# var_state_eq.net
KiCad netlist of a schematic drawn in EAGLE
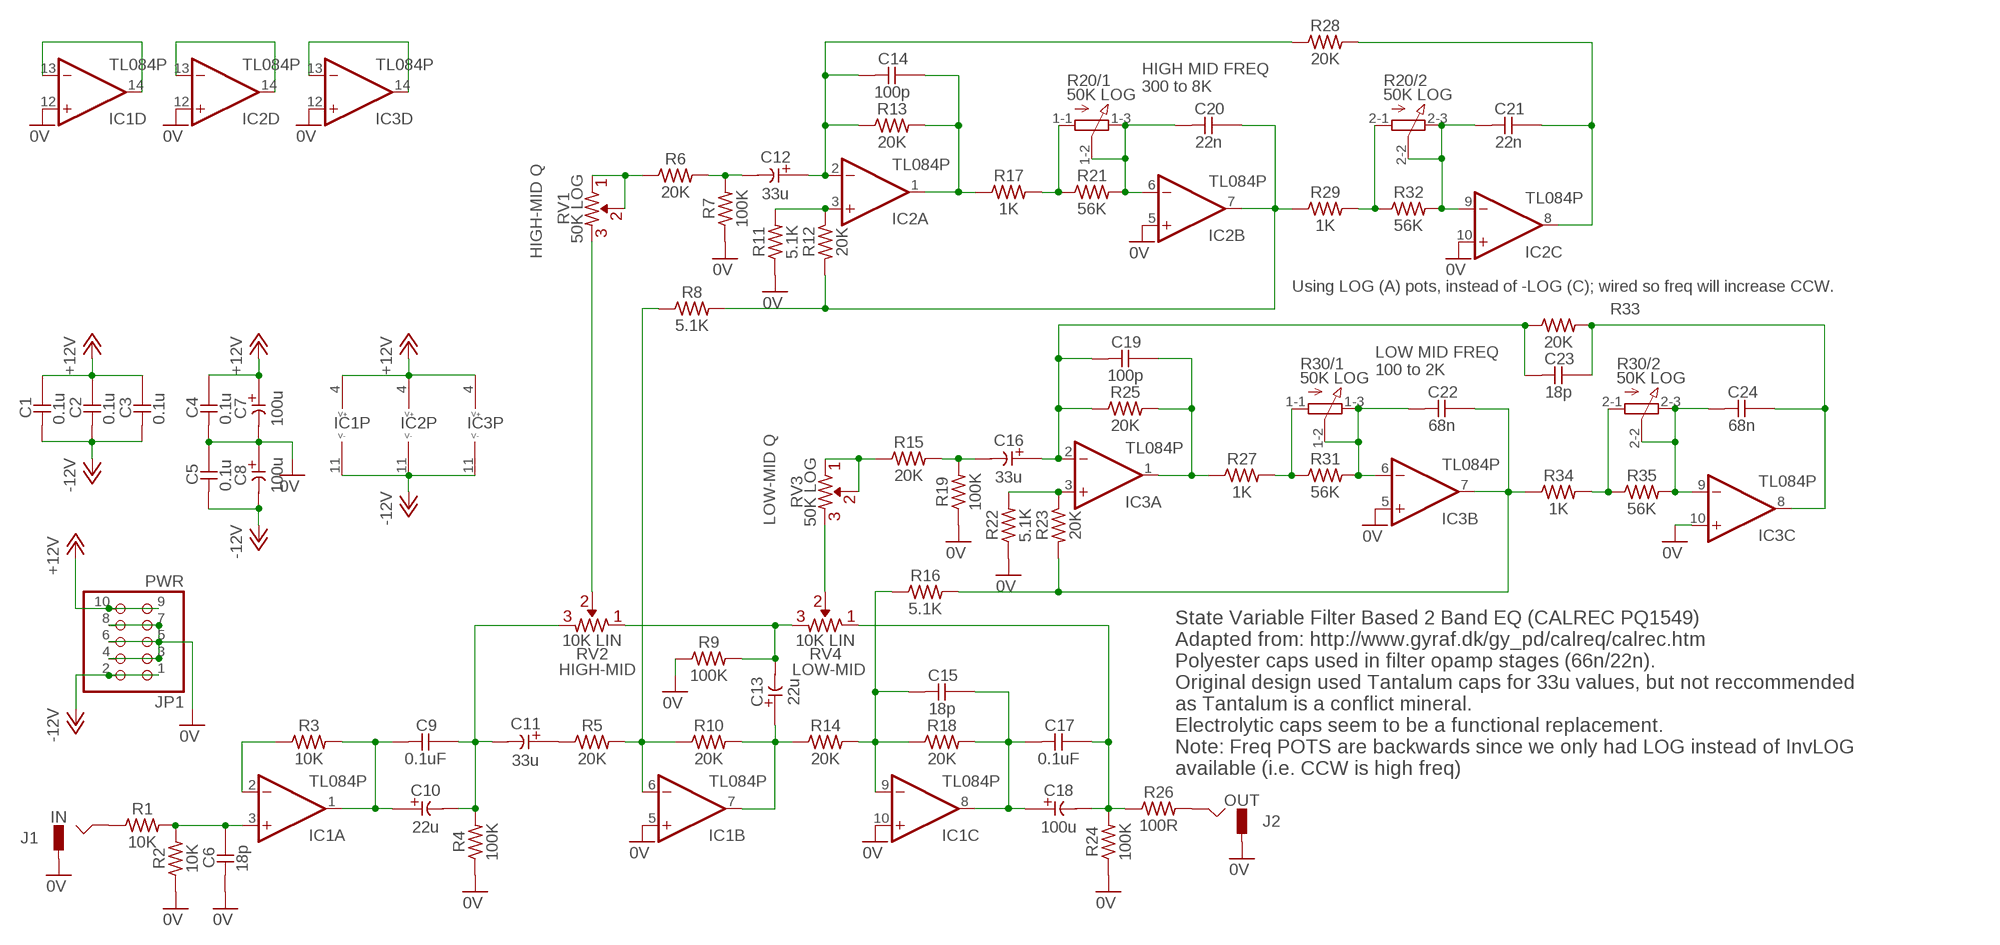
[diagram p0: schematic, sheet 1]

(export (version "E")
  (design (tool "Eeschema 10.0.6"))
  (components
    (comp (ref "C1")
      (value "0.1u")
      (footprint "eagle-import:C025-024X044")
      (libsource (lib "eagle-import") (part "CC-US025-024X044"))
    )
    (comp (ref "C2")
      (value "0.1u")
      (footprint "eagle-import:C025-024X044")
      (libsource (lib "eagle-import") (part "CC-US025-024X044"))
    )
    (comp (ref "C3")
      (value "0.1u")
      (footprint "eagle-import:C025-024X044")
      (libsource (lib "eagle-import") (part "CC-US025-024X044"))
    )
    (comp (ref "C4")
      (value "0.1u")
      (footprint "eagle-import:C025-024X044")
      (libsource (lib "eagle-import") (part "CC-US025-024X044"))
    )
    (comp (ref "C5")
      (value "0.1u")
      (footprint "eagle-import:C025-024X044")
      (libsource (lib "eagle-import") (part "CC-US025-024X044"))
    )
    (comp (ref "C6")
      (value "18p")
      (footprint "eagle-import:C025-024X044")
      (libsource (lib "eagle-import") (part "CC-US025-024X044"))
    )
    (comp (ref "C7")
      (value "100u")
      (footprint "eagle-import:E5-8,5")
      (libsource (lib "eagle-import") (part "CE-USE5-8.5"))
    )
    (comp (ref "C8")
      (value "100u")
      (footprint "eagle-import:E5-8,5")
      (libsource (lib "eagle-import") (part "CE-USE5-8.5"))
    )
    (comp (ref "C9")
      (value "0.1uF")
      (footprint "eagle-import:C025-024X044")
      (libsource (lib "eagle-import") (part "CC-US025-024X044"))
    )
    (comp (ref "C10")
      (value "22u")
      (footprint "eagle-import:E2-5")
      (libsource (lib "eagle-import") (part "CE-USE2-5"))
    )
    (comp (ref "C11")
      (value "33u")
      (footprint "eagle-import:E2-5")
      (libsource (lib "eagle-import") (part "CE-USE2-5"))
    )
    (comp (ref "C12")
      (value "33u")
      (footprint "eagle-import:E2-5")
      (libsource (lib "eagle-import") (part "CE-USE2-5"))
    )
    (comp (ref "C13")
      (value "22u")
      (footprint "eagle-import:E2-5")
      (libsource (lib "eagle-import") (part "CE-USE2-5"))
    )
    (comp (ref "C14")
      (value "100p")
      (footprint "eagle-import:C025-024X044")
      (libsource (lib "eagle-import") (part "CC-US025-024X044"))
    )
    (comp (ref "C15")
      (value "18p")
      (footprint "eagle-import:C025-024X044")
      (libsource (lib "eagle-import") (part "CC-US025-024X044"))
    )
    (comp (ref "C16")
      (value "33u")
      (footprint "eagle-import:E2-5")
      (libsource (lib "eagle-import") (part "CE-USE2-5"))
    )
    (comp (ref "C17")
      (value "0.1uF")
      (footprint "eagle-import:C025-024X044")
      (libsource (lib "eagle-import") (part "CC-US025-024X044"))
    )
    (comp (ref "C18")
      (value "100u")
      (footprint "eagle-import:E5-8,5")
      (libsource (lib "eagle-import") (part "CE-USE5-8.5"))
    )
    (comp (ref "C19")
      (value "100p")
      (footprint "eagle-import:C025-024X044")
      (libsource (lib "eagle-import") (part "CC-US025-024X044"))
    )
    (comp (ref "C20")
      (value "22n")
      (footprint "eagle-import:C050-024X044")
      (libsource (lib "eagle-import") (part "CC-US050-024X044"))
    )
    (comp (ref "C21")
      (value "22n")
      (footprint "eagle-import:C050-024X044")
      (libsource (lib "eagle-import") (part "CC-US050-024X044"))
    )
    (comp (ref "C22")
      (value "68n")
      (footprint "eagle-import:C050-024X044")
      (libsource (lib "eagle-import") (part "CC-US050-024X044"))
    )
    (comp (ref "C23")
      (value "18p")
      (footprint "eagle-import:C025-024X044")
      (libsource (lib "eagle-import") (part "CC-US025-024X044"))
    )
    (comp (ref "C24")
      (value "68n")
      (footprint "eagle-import:C050-024X044")
      (libsource (lib "eagle-import") (part "CC-US050-024X044"))
    )
    (comp (ref "IC1")
      (value "TL084P")
      (footprint "eagle-import:DIL14")
      (libsource (lib "eagle-import") (part "TL084P"))
    )
    (comp (ref "IC2")
      (value "TL084P")
      (footprint "eagle-import:DIL14")
      (libsource (lib "eagle-import") (part "TL084P"))
    )
    (comp (ref "IC3")
      (value "TL084P")
      (footprint "eagle-import:DIL14")
      (libsource (lib "eagle-import") (part "TL084P"))
    )
    (comp (ref "J1")
      (value "IN")
      (footprint "eagle-import:JACK-M")
      (libsource (lib "eagle-import") (part "JACK-M"))
    )
    (comp (ref "J2")
      (value "OUT")
      (footprint "eagle-import:JACK-M")
      (libsource (lib "eagle-import") (part "JACK-M"))
    )
    (comp (ref "JP1")
      (value "PWR")
      (footprint "eagle-import:2X05")
      (libsource (lib "eagle-import") (part "PINHD-2X5"))
    )
    (comp (ref "R1")
      (value "10K")
      (footprint "eagle-import:0207_7")
      (libsource (lib "eagle-import") (part "R"))
    )
    (comp (ref "R2")
      (value "10K")
      (footprint "eagle-import:0207_7")
      (libsource (lib "eagle-import") (part "R"))
    )
    (comp (ref "R3")
      (value "10K")
      (footprint "eagle-import:0207_7")
      (libsource (lib "eagle-import") (part "R"))
    )
    (comp (ref "R4")
      (value "100K")
      (footprint "eagle-import:0207_7")
      (libsource (lib "eagle-import") (part "R"))
    )
    (comp (ref "R5")
      (value "20K")
      (footprint "eagle-import:0207_7")
      (libsource (lib "eagle-import") (part "R"))
    )
    (comp (ref "R6")
      (value "20K")
      (footprint "eagle-import:0207_7")
      (libsource (lib "eagle-import") (part "R"))
    )
    (comp (ref "R7")
      (value "100K")
      (footprint "eagle-import:0207_7")
      (libsource (lib "eagle-import") (part "R"))
    )
    (comp (ref "R8")
      (value "5.1K")
      (footprint "eagle-import:0207_7")
      (libsource (lib "eagle-import") (part "R"))
    )
    (comp (ref "R9")
      (value "100K")
      (footprint "eagle-import:0207_7")
      (libsource (lib "eagle-import") (part "R"))
    )
    (comp (ref "R10")
      (value "20K")
      (footprint "eagle-import:0207_7")
      (libsource (lib "eagle-import") (part "R"))
    )
    (comp (ref "R11")
      (value "5.1K")
      (footprint "eagle-import:0207_7")
      (libsource (lib "eagle-import") (part "R"))
    )
    (comp (ref "R12")
      (value "20K")
      (footprint "eagle-import:0207_7")
      (libsource (lib "eagle-import") (part "R"))
    )
    (comp (ref "R13")
      (value "20K")
      (footprint "eagle-import:0207_7")
      (libsource (lib "eagle-import") (part "R"))
    )
    (comp (ref "R14")
      (value "20K")
      (footprint "eagle-import:0207_7")
      (libsource (lib "eagle-import") (part "R"))
    )
    (comp (ref "R15")
      (value "20K")
      (footprint "eagle-import:0207_7")
      (libsource (lib "eagle-import") (part "R"))
    )
    (comp (ref "R16")
      (value "5.1K")
      (footprint "eagle-import:0207_7")
      (libsource (lib "eagle-import") (part "R"))
    )
    (comp (ref "R17")
      (value "1K")
      (footprint "eagle-import:0207_7")
      (libsource (lib "eagle-import") (part "R"))
    )
    (comp (ref "R18")
      (value "20K")
      (footprint "eagle-import:0207_7")
      (libsource (lib "eagle-import") (part "R"))
    )
    (comp (ref "R19")
      (value "100K")
      (footprint "eagle-import:0207_7")
      (libsource (lib "eagle-import") (part "R"))
    )
    (comp (ref "R20")
      (value "50K LOG")
      (footprint "eagle-import:3RP_1610G")
      (libsource (lib "eagle-import") (part "3RP/1610G"))
    )
    (comp (ref "R21")
      (value "56K")
      (footprint "eagle-import:0207_7")
      (libsource (lib "eagle-import") (part "R"))
    )
    (comp (ref "R22")
      (value "5.1K")
      (footprint "eagle-import:0207_7")
      (libsource (lib "eagle-import") (part "R"))
    )
    (comp (ref "R23")
      (value "20K")
      (footprint "eagle-import:0207_7")
      (libsource (lib "eagle-import") (part "R"))
    )
    (comp (ref "R24")
      (value "100K")
      (footprint "eagle-import:0207_7")
      (libsource (lib "eagle-import") (part "R"))
    )
    (comp (ref "R25")
      (value "20K")
      (footprint "eagle-import:0207_7")
      (libsource (lib "eagle-import") (part "R"))
    )
    (comp (ref "R26")
      (value "100R")
      (footprint "eagle-import:0207_7")
      (libsource (lib "eagle-import") (part "R"))
    )
    (comp (ref "R27")
      (value "1K")
      (footprint "eagle-import:0207_7")
      (libsource (lib "eagle-import") (part "R"))
    )
    (comp (ref "R28")
      (value "20K")
      (footprint "eagle-import:0207_7")
      (libsource (lib "eagle-import") (part "R"))
    )
    (comp (ref "R29")
      (value "1K")
      (footprint "eagle-import:0207_7")
      (libsource (lib "eagle-import") (part "R"))
    )
    (comp (ref "R30")
      (value "50K LOG")
      (footprint "eagle-import:3RP_1610G")
      (libsource (lib "eagle-import") (part "3RP/1610G"))
    )
    (comp (ref "R31")
      (value "56K")
      (footprint "eagle-import:0207_7")
      (libsource (lib "eagle-import") (part "R"))
    )
    (comp (ref "R32")
      (value "56K")
      (footprint "eagle-import:0207_7")
      (libsource (lib "eagle-import") (part "R"))
    )
    (comp (ref "R33")
      (value "20K")
      (footprint "eagle-import:0207_7")
      (libsource (lib "eagle-import") (part "R"))
    )
    (comp (ref "R34")
      (value "1K")
      (footprint "eagle-import:0207_7")
      (libsource (lib "eagle-import") (part "R"))
    )
    (comp (ref "R35")
      (value "56K")
      (footprint "eagle-import:0207_7")
      (libsource (lib "eagle-import") (part "R"))
    )
    (comp (ref "RV1")
      (value "50K LOG")
      (footprint "eagle-import:R-VAR-PANEL")
      (libsource (lib "eagle-import") (part "R-VAR-PANEL"))
    )
    (comp (ref "RV2")
      (value "10K LIN")
      (footprint "eagle-import:R-VAR-PANEL")
      (libsource (lib "eagle-import") (part "R-VAR-PANEL"))
    )
    (comp (ref "RV3")
      (value "50K LOG")
      (footprint "eagle-import:R-VAR-PANEL")
      (libsource (lib "eagle-import") (part "R-VAR-PANEL"))
    )
    (comp (ref "RV4")
      (value "10K LIN")
      (footprint "eagle-import:R-VAR-PANEL")
      (libsource (lib "eagle-import") (part "R-VAR-PANEL"))
    )
  )
  (nets
    (net (code "1") (name "+12V") (class "Default")
      (node (ref "C1") (pin "1") (pinfunction "1_1") (pintype "passive"))
      (node (ref "C2") (pin "1") (pinfunction "1_1") (pintype "passive"))
      (node (ref "C3") (pin "1") (pinfunction "1_1") (pintype "passive"))
      (node (ref "C4") (pin "1") (pinfunction "1_1") (pintype "passive"))
      (node (ref "C7") (pin "+") (pinfunction "+_+") (pintype "passive"))
      (node (ref "IC1") (pin "4") (pinfunction "V+_4") (pintype "power_in"))
      (node (ref "IC2") (pin "4") (pinfunction "V+_4") (pintype "power_in"))
      (node (ref "IC3") (pin "4") (pinfunction "V+_4") (pintype "power_in"))
      (node (ref "JP1") (pin "10") (pinfunction "10_10") (pintype "passive"))
      (node (ref "JP1") (pin "9") (pinfunction "9_9") (pintype "passive"))
    )
    (net (code "2") (name "-12V") (class "Default")
      (node (ref "C1") (pin "2") (pinfunction "2_2") (pintype "passive"))
      (node (ref "C2") (pin "2") (pinfunction "2_2") (pintype "passive"))
      (node (ref "C3") (pin "2") (pinfunction "2_2") (pintype "passive"))
      (node (ref "C5") (pin "2") (pinfunction "2_2") (pintype "passive"))
      (node (ref "C8") (pin "-") (pinfunction "-_-") (pintype "passive"))
      (node (ref "IC1") (pin "11") (pinfunction "V-_11") (pintype "power_in"))
      (node (ref "IC2") (pin "11") (pinfunction "V-_11") (pintype "power_in"))
      (node (ref "IC3") (pin "11") (pinfunction "V-_11") (pintype "power_in"))
      (node (ref "JP1") (pin "1") (pinfunction "1_1") (pintype "passive"))
      (node (ref "JP1") (pin "2") (pinfunction "2_2") (pintype "passive"))
    )
    (net (code "3") (name "0V") (class "Default")
      (node (ref "C4") (pin "2") (pinfunction "2_2") (pintype "passive"))
      (node (ref "C5") (pin "1") (pinfunction "1_1") (pintype "passive"))
      (node (ref "C6") (pin "2") (pinfunction "2_2") (pintype "passive"))
      (node (ref "C7") (pin "-") (pinfunction "-_-") (pintype "passive"))
      (node (ref "C8") (pin "+") (pinfunction "+_+") (pintype "passive"))
      (node (ref "IC1") (pin "10") (pinfunction "+IN_10") (pintype "input"))
      (node (ref "IC1") (pin "12") (pinfunction "+IN_12") (pintype "input"))
      (node (ref "IC1") (pin "5") (pinfunction "+IN_5") (pintype "input"))
      (node (ref "IC2") (pin "10") (pinfunction "+IN_10") (pintype "input"))
      (node (ref "IC2") (pin "12") (pinfunction "+IN_12") (pintype "input"))
      (node (ref "IC2") (pin "5") (pinfunction "+IN_5") (pintype "input"))
      (node (ref "IC3") (pin "10") (pinfunction "+IN_10") (pintype "input"))
      (node (ref "IC3") (pin "12") (pinfunction "+IN_12") (pintype "input"))
      (node (ref "IC3") (pin "5") (pinfunction "+IN_5") (pintype "input"))
      (node (ref "J1") (pin "GND") (pinfunction "GND_GND") (pintype "bidirectional"))
      (node (ref "J2") (pin "GND") (pinfunction "GND_GND") (pintype "bidirectional"))
      (node (ref "JP1") (pin "3") (pinfunction "3_3") (pintype "passive"))
      (node (ref "JP1") (pin "4") (pinfunction "4_4") (pintype "passive"))
      (node (ref "JP1") (pin "5") (pinfunction "5_5") (pintype "passive"))
      (node (ref "JP1") (pin "6") (pinfunction "6_6") (pintype "passive"))
      (node (ref "JP1") (pin "7") (pinfunction "7_7") (pintype "passive"))
      (node (ref "JP1") (pin "8") (pinfunction "8_8") (pintype "passive"))
      (node (ref "R11") (pin "1") (pinfunction "1_1") (pintype "passive"))
      (node (ref "R19") (pin "1") (pinfunction "1_1") (pintype "passive"))
      (node (ref "R2") (pin "1") (pinfunction "1_1") (pintype "passive"))
      (node (ref "R22") (pin "1") (pinfunction "1_1") (pintype "passive"))
      (node (ref "R24") (pin "1") (pinfunction "1_1") (pintype "passive"))
      (node (ref "R4") (pin "1") (pinfunction "1_1") (pintype "passive"))
      (node (ref "R7") (pin "1") (pinfunction "1_1") (pintype "passive"))
      (node (ref "R9") (pin "1") (pinfunction "1_1") (pintype "passive"))
    )
    (net (code "4") (name "Net-(C11-Pad+)") (class "Default")
      (node (ref "C11") (pin "+") (pinfunction "+_+") (pintype "passive"))
      (node (ref "R5") (pin "1") (pinfunction "1_1") (pintype "passive"))
    )
    (net (code "5") (name "Net-(C12-Pad-)") (class "Default")
      (node (ref "C12") (pin "-") (pinfunction "-_-") (pintype "passive"))
      (node (ref "R6") (pin "2") (pinfunction "2_2") (pintype "passive"))
      (node (ref "R7") (pin "2") (pinfunction "2_2") (pintype "passive"))
    )
    (net (code "6") (name "Net-(C16-Pad-)") (class "Default")
      (node (ref "C16") (pin "-") (pinfunction "-_-") (pintype "passive"))
      (node (ref "R15") (pin "2") (pinfunction "2_2") (pintype "passive"))
      (node (ref "R19") (pin "2") (pinfunction "2_2") (pintype "passive"))
    )
    (net (code "7") (name "Net-(IC1A-+IN)") (class "Default")
      (node (ref "C6") (pin "1") (pinfunction "1_1") (pintype "passive"))
      (node (ref "IC1") (pin "3") (pinfunction "+IN_3") (pintype "input"))
      (node (ref "R1") (pin "2") (pinfunction "2_2") (pintype "passive"))
      (node (ref "R2") (pin "2") (pinfunction "2_2") (pintype "passive"))
    )
    (net (code "8") (name "Net-(IC1A--IN)") (class "Default")
      (node (ref "IC1") (pin "2") (pinfunction "-IN_2") (pintype "input"))
      (node (ref "R3") (pin "1") (pinfunction "1_1") (pintype "passive"))
    )
    (net (code "9") (name "Net-(IC1A-OUT)") (class "Default")
      (node (ref "C10") (pin "+") (pinfunction "+_+") (pintype "passive"))
      (node (ref "C9") (pin "2") (pinfunction "2_2") (pintype "passive"))
      (node (ref "IC1") (pin "1") (pinfunction "OUT_1") (pintype "output"))
      (node (ref "R3") (pin "2") (pinfunction "2_2") (pintype "passive"))
    )
    (net (code "10") (name "Net-(IC1B--IN)") (class "Default")
      (node (ref "IC1") (pin "6") (pinfunction "-IN_6") (pintype "input"))
      (node (ref "R10") (pin "1") (pinfunction "1_1") (pintype "passive"))
      (node (ref "R5") (pin "2") (pinfunction "2_2") (pintype "passive"))
      (node (ref "R8") (pin "1") (pinfunction "1_1") (pintype "passive"))
    )
    (net (code "11") (name "Net-(IC1B-OUT)") (class "Default")
      (node (ref "C13") (pin "+") (pinfunction "+_+") (pintype "passive"))
      (node (ref "IC1") (pin "7") (pinfunction "OUT_7") (pintype "output"))
      (node (ref "R10") (pin "2") (pinfunction "2_2") (pintype "passive"))
      (node (ref "R14") (pin "1") (pinfunction "1_1") (pintype "passive"))
    )
    (net (code "12") (name "Net-(IC1C--IN)") (class "Default")
      (node (ref "C15") (pin "2") (pinfunction "2_2") (pintype "passive"))
      (node (ref "IC1") (pin "9") (pinfunction "-IN_9") (pintype "input"))
      (node (ref "R14") (pin "2") (pinfunction "2_2") (pintype "passive"))
      (node (ref "R16") (pin "1") (pinfunction "1_1") (pintype "passive"))
      (node (ref "R18") (pin "1") (pinfunction "1_1") (pintype "passive"))
    )
    (net (code "13") (name "Net-(IC1C-OUT)") (class "Default")
      (node (ref "C15") (pin "1") (pinfunction "1_1") (pintype "passive"))
      (node (ref "C17") (pin "2") (pinfunction "2_2") (pintype "passive"))
      (node (ref "C18") (pin "+") (pinfunction "+_+") (pintype "passive"))
      (node (ref "IC1") (pin "8") (pinfunction "OUT_8") (pintype "output"))
      (node (ref "R18") (pin "2") (pinfunction "2_2") (pintype "passive"))
    )
    (net (code "14") (name "Net-(IC1D--IN)") (class "Default")
      (node (ref "IC1") (pin "13") (pinfunction "-IN_13") (pintype "input"))
      (node (ref "IC1") (pin "14") (pinfunction "OUT_14") (pintype "output"))
    )
    (net (code "15") (name "Net-(IC2A-+IN)") (class "Default")
      (node (ref "IC2") (pin "3") (pinfunction "+IN_3") (pintype "input"))
      (node (ref "R11") (pin "2") (pinfunction "2_2") (pintype "passive"))
      (node (ref "R12") (pin "1") (pinfunction "1_1") (pintype "passive"))
    )
    (net (code "16") (name "Net-(IC2A--IN)") (class "Default")
      (node (ref "C12") (pin "+") (pinfunction "+_+") (pintype "passive"))
      (node (ref "C14") (pin "2") (pinfunction "2_2") (pintype "passive"))
      (node (ref "IC2") (pin "2") (pinfunction "-IN_2") (pintype "input"))
      (node (ref "R13") (pin "1") (pinfunction "1_1") (pintype "passive"))
      (node (ref "R28") (pin "1") (pinfunction "1_1") (pintype "passive"))
    )
    (net (code "17") (name "Net-(IC2A-OUT)") (class "Default")
      (node (ref "C14") (pin "1") (pinfunction "1_1") (pintype "passive"))
      (node (ref "IC2") (pin "1") (pinfunction "OUT_1") (pintype "output"))
      (node (ref "R13") (pin "2") (pinfunction "2_2") (pintype "passive"))
      (node (ref "R17") (pin "1") (pinfunction "1_1") (pintype "passive"))
    )
    (net (code "18") (name "Net-(IC2B--IN)") (class "Default")
      (node (ref "C20") (pin "2") (pinfunction "2_2") (pintype "passive"))
      (node (ref "IC2") (pin "6") (pinfunction "-IN_6") (pintype "input"))
      (node (ref "R20") (pin "1-2") (pinfunction "S_1-2") (pintype "passive"))
      (node (ref "R20") (pin "1-3") (pinfunction "E_1-3") (pintype "passive"))
      (node (ref "R21") (pin "2") (pinfunction "2_2") (pintype "passive"))
    )
    (net (code "19") (name "Net-(IC2B-OUT)") (class "Default")
      (node (ref "C20") (pin "1") (pinfunction "1_1") (pintype "passive"))
      (node (ref "IC2") (pin "7") (pinfunction "OUT_7") (pintype "output"))
      (node (ref "R12") (pin "2") (pinfunction "2_2") (pintype "passive"))
      (node (ref "R29") (pin "1") (pinfunction "1_1") (pintype "passive"))
      (node (ref "R8") (pin "2") (pinfunction "2_2") (pintype "passive"))
    )
    (net (code "20") (name "Net-(IC2C--IN)") (class "Default")
      (node (ref "C21") (pin "2") (pinfunction "2_2") (pintype "passive"))
      (node (ref "IC2") (pin "9") (pinfunction "-IN_9") (pintype "input"))
      (node (ref "R20") (pin "2-2") (pinfunction "S_2-2") (pintype "passive"))
      (node (ref "R20") (pin "2-3") (pinfunction "E_2-3") (pintype "passive"))
      (node (ref "R32") (pin "2") (pinfunction "2_2") (pintype "passive"))
    )
    (net (code "21") (name "Net-(IC2C-OUT)") (class "Default")
      (node (ref "C21") (pin "1") (pinfunction "1_1") (pintype "passive"))
      (node (ref "IC2") (pin "8") (pinfunction "OUT_8") (pintype "output"))
      (node (ref "R28") (pin "2") (pinfunction "2_2") (pintype "passive"))
    )
    (net (code "22") (name "Net-(IC2D--IN)") (class "Default")
      (node (ref "IC2") (pin "13") (pinfunction "-IN_13") (pintype "input"))
      (node (ref "IC2") (pin "14") (pinfunction "OUT_14") (pintype "output"))
    )
    (net (code "23") (name "Net-(IC3A-+IN)") (class "Default")
      (node (ref "IC3") (pin "3") (pinfunction "+IN_3") (pintype "input"))
      (node (ref "R22") (pin "2") (pinfunction "2_2") (pintype "passive"))
      (node (ref "R23") (pin "1") (pinfunction "1_1") (pintype "passive"))
    )
    (net (code "24") (name "Net-(IC3A--IN)") (class "Default")
      (node (ref "C16") (pin "+") (pinfunction "+_+") (pintype "passive"))
      (node (ref "C19") (pin "2") (pinfunction "2_2") (pintype "passive"))
      (node (ref "C23") (pin "2") (pinfunction "2_2") (pintype "passive"))
      (node (ref "IC3") (pin "2") (pinfunction "-IN_2") (pintype "input"))
      (node (ref "R25") (pin "1") (pinfunction "1_1") (pintype "passive"))
      (node (ref "R33") (pin "1") (pinfunction "1_1") (pintype "passive"))
    )
    (net (code "25") (name "Net-(IC3A-OUT)") (class "Default")
      (node (ref "C19") (pin "1") (pinfunction "1_1") (pintype "passive"))
      (node (ref "IC3") (pin "1") (pinfunction "OUT_1") (pintype "output"))
      (node (ref "R25") (pin "2") (pinfunction "2_2") (pintype "passive"))
      (node (ref "R27") (pin "1") (pinfunction "1_1") (pintype "passive"))
    )
    (net (code "26") (name "Net-(IC3B--IN)") (class "Default")
      (node (ref "C22") (pin "2") (pinfunction "2_2") (pintype "passive"))
      (node (ref "IC3") (pin "6") (pinfunction "-IN_6") (pintype "input"))
      (node (ref "R30") (pin "1-2") (pinfunction "S_1-2") (pintype "passive"))
      (node (ref "R30") (pin "1-3") (pinfunction "E_1-3") (pintype "passive"))
      (node (ref "R31") (pin "2") (pinfunction "2_2") (pintype "passive"))
    )
    (net (code "27") (name "Net-(IC3B-OUT)") (class "Default")
      (node (ref "C22") (pin "1") (pinfunction "1_1") (pintype "passive"))
      (node (ref "IC3") (pin "7") (pinfunction "OUT_7") (pintype "output"))
      (node (ref "R16") (pin "2") (pinfunction "2_2") (pintype "passive"))
      (node (ref "R23") (pin "2") (pinfunction "2_2") (pintype "passive"))
      (node (ref "R34") (pin "1") (pinfunction "1_1") (pintype "passive"))
    )
    (net (code "28") (name "Net-(IC3C--IN)") (class "Default")
      (node (ref "C24") (pin "2") (pinfunction "2_2") (pintype "passive"))
      (node (ref "IC3") (pin "9") (pinfunction "-IN_9") (pintype "input"))
      (node (ref "R30") (pin "2-2") (pinfunction "S_2-2") (pintype "passive"))
      (node (ref "R30") (pin "2-3") (pinfunction "E_2-3") (pintype "passive"))
      (node (ref "R35") (pin "2") (pinfunction "2_2") (pintype "passive"))
    )
    (net (code "29") (name "Net-(IC3C-OUT)") (class "Default")
      (node (ref "C23") (pin "1") (pinfunction "1_1") (pintype "passive"))
      (node (ref "C24") (pin "1") (pinfunction "1_1") (pintype "passive"))
      (node (ref "IC3") (pin "8") (pinfunction "OUT_8") (pintype "output"))
      (node (ref "R33") (pin "2") (pinfunction "2_2") (pintype "passive"))
    )
    (net (code "30") (name "Net-(IC3D--IN)") (class "Default")
      (node (ref "IC3") (pin "13") (pinfunction "-IN_13") (pintype "input"))
      (node (ref "IC3") (pin "14") (pinfunction "OUT_14") (pintype "output"))
    )
    (net (code "31") (name "Net-(J1-PadHOT)") (class "Default")
      (node (ref "J1") (pin "HOT") (pinfunction "HOT_HOT") (pintype "bidirectional"))
      (node (ref "R1") (pin "1") (pinfunction "1_1") (pintype "passive"))
    )
    (net (code "32") (name "Net-(J2-PadHOT)") (class "Default")
      (node (ref "J2") (pin "HOT") (pinfunction "HOT_HOT") (pintype "bidirectional"))
      (node (ref "R26") (pin "2") (pinfunction "2_2") (pintype "passive"))
    )
    (net (code "33") (name "Net-(R20A-A)") (class "Default")
      (node (ref "R17") (pin "2") (pinfunction "2_2") (pintype "passive"))
      (node (ref "R20") (pin "1-1") (pinfunction "A_1-1") (pintype "passive"))
      (node (ref "R21") (pin "1") (pinfunction "1_1") (pintype "passive"))
    )
    (net (code "34") (name "Net-(R20B-A)") (class "Default")
      (node (ref "R20") (pin "2-1") (pinfunction "A_2-1") (pintype "passive"))
      (node (ref "R29") (pin "2") (pinfunction "2_2") (pintype "passive"))
      (node (ref "R32") (pin "1") (pinfunction "1_1") (pintype "passive"))
    )
    (net (code "35") (name "Net-(R30A-A)") (class "Default")
      (node (ref "R27") (pin "2") (pinfunction "2_2") (pintype "passive"))
      (node (ref "R30") (pin "1-1") (pinfunction "A_1-1") (pintype "passive"))
      (node (ref "R31") (pin "1") (pinfunction "1_1") (pintype "passive"))
    )
    (net (code "36") (name "Net-(R30B-A)") (class "Default")
      (node (ref "R30") (pin "2-1") (pinfunction "A_2-1") (pintype "passive"))
      (node (ref "R34") (pin "2") (pinfunction "2_2") (pintype "passive"))
      (node (ref "R35") (pin "1") (pinfunction "1_1") (pintype "passive"))
    )
    (net (code "37") (name "Net-(RV1-1)") (class "Default")
      (node (ref "R6") (pin "1") (pinfunction "1_1") (pintype "passive"))
      (node (ref "RV1") (pin "R1") (pinfunction "1_R1") (pintype "passive"))
      (node (ref "RV1") (pin "VAR") (pinfunction "P$1_VAR") (pintype "passive"))
    )
    (net (code "38") (name "Net-(RV1-2)") (class "Default")
      (node (ref "RV1") (pin "R2") (pinfunction "2_R2") (pintype "passive"))
      (node (ref "RV2") (pin "VAR") (pinfunction "P$1_VAR") (pintype "passive"))
    )
    (net (code "39") (name "Net-(RV2-1)") (class "Default")
      (node (ref "C13") (pin "-") (pinfunction "-_-") (pintype "passive"))
      (node (ref "R9") (pin "2") (pinfunction "2_2") (pintype "passive"))
      (node (ref "RV2") (pin "R1") (pinfunction "1_R1") (pintype "passive"))
      (node (ref "RV4") (pin "R2") (pinfunction "2_R2") (pintype "passive"))
    )
    (net (code "40") (name "Net-(RV2-2)") (class "Default")
      (node (ref "C10") (pin "-") (pinfunction "-_-") (pintype "passive"))
      (node (ref "C11") (pin "-") (pinfunction "-_-") (pintype "passive"))
      (node (ref "C9") (pin "1") (pinfunction "1_1") (pintype "passive"))
      (node (ref "R4") (pin "2") (pinfunction "2_2") (pintype "passive"))
      (node (ref "RV2") (pin "R2") (pinfunction "2_R2") (pintype "passive"))
    )
    (net (code "41") (name "Net-(RV3-1)") (class "Default")
      (node (ref "R15") (pin "1") (pinfunction "1_1") (pintype "passive"))
      (node (ref "RV3") (pin "R1") (pinfunction "1_R1") (pintype "passive"))
      (node (ref "RV3") (pin "VAR") (pinfunction "P$1_VAR") (pintype "passive"))
    )
    (net (code "42") (name "Net-(RV3-2)") (class "Default")
      (node (ref "RV3") (pin "R2") (pinfunction "2_R2") (pintype "passive"))
      (node (ref "RV4") (pin "VAR") (pinfunction "P$1_VAR") (pintype "passive"))
    )
    (net (code "43") (name "Net-(RV4-1)") (class "Default")
      (node (ref "C17") (pin "1") (pinfunction "1_1") (pintype "passive"))
      (node (ref "C18") (pin "-") (pinfunction "-_-") (pintype "passive"))
      (node (ref "R24") (pin "2") (pinfunction "2_2") (pintype "passive"))
      (node (ref "R26") (pin "1") (pinfunction "1_1") (pintype "passive"))
      (node (ref "RV4") (pin "R1") (pinfunction "1_R1") (pintype "passive"))
    )
  )
)
